# interfaceUART_I2C.net
KiCad netlist of a schematic drawn in Altium Designer
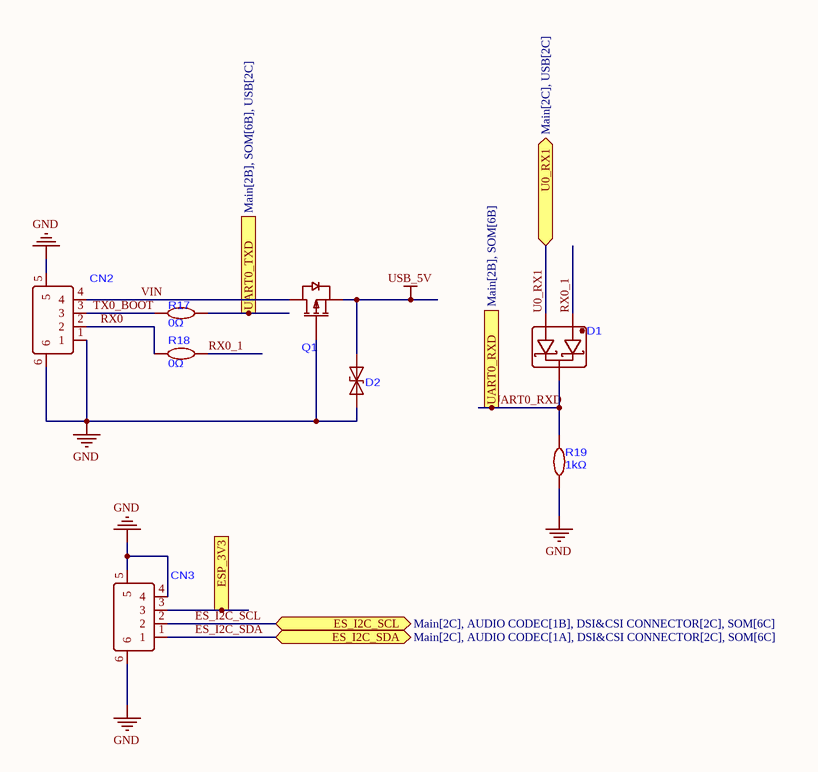
[diagram p0: interfaceUART&I2C.SchDoc]

(export (version "E")
  (design (tool "Eeschema 10.0.6"))
  (components
    (comp (ref "CN2")
      (value "533980471")
      (footprint "CONN-SMD_4P-P1.25_XUNPU_WAFER-GH1.25-4PWB")
      (libsource (lib "Schlib2") (part "533980471"))
    )
    (comp (ref "CN3")
      (value "533980471")
      (footprint "CONN-SMD_4P-P1.25_XUNPU_WAFER-GH1.25-4PWB")
      (libsource (lib "Schlib2") (part "533980471"))
    )
    (comp (ref "D1")
      (value "DIODE ARR SCHOTTKY 30V SOT-23")
      (footprint "SOT-23-3_L2.9-W1.3-P1.90-LS2.4-BR")
      (description "600mA 30V 1 Pair Common Cathode 1V@100mA 200mA SOT-23 Single Diodes RoHS")
      (libsource (lib "Schlib2") (part "BAT54C_C916424"))
    )
    (comp (ref "D2")
      (value "TVS DIODE 5VWM 18.6VC SOD-523")
      (footprint "SOD-523_L1.2-W0.8-LS1.6-BI")
      (description "9.4A@8/20us 18.6V 7.8V 5V SOD-523 TVS Diodes RoHS")
      (libsource (lib "Schlib2") (part "LESD5D5.0CT1G"))
    )
    (comp (ref "Q1")
      (value "MOSFET P-CH 30V 4.3A SOT-23")
      (footprint "2SOT-23-3_L2.9-W1.6-P1.90-LS2.8-BR")
      (description "30V 4.3A 48mΩ@10V 2.5V@250uA 1 P-Channel SOT-23 Single FETs, MOSFETs ROHS")
      (libsource (lib "Schlib2") (part "AO3407A"))
    )
    (comp (ref "R17")
      (value "0Ω")
      (footprint "R0603")
      (description "100mW 0Ω 75V Thick Film Resistor ±5% 0603 Chip Resistor - Surface Mount RoHS")
      (libsource (lib "Schlib2") (part "RC0603JR-070RL"))
    )
    (comp (ref "R18")
      (value "0Ω")
      (footprint "R0603")
      (description "100mW 0Ω 75V Thick Film Resistor ±5% 0603 Chip Resistor - Surface Mount RoHS")
      (libsource (lib "Schlib2") (part "RC0603JR-070RL"))
    )
    (comp (ref "R19")
      (value "1kΩ")
      (footprint "R0603")
      (description "100mW 1kΩ 50V ±100ppm/℃ Thick Film Resistor ±5% 0603 Chip Resistor - Surface Mount ROHS")
      (libsource (lib "Schlib2") (part "RMC 0603 1K J N"))
    )
  )
  (nets
    (net (code "1") (name "/ESP_3V3") (class "Default")
      (node (ref "CN3") (pin "3") (pinfunction "3_3") (pintype "passive"))
    )
    (net (code "2") (name "/ES_I2C_SCL") (class "Default")
      (node (ref "CN3") (pin "2") (pinfunction "2_2") (pintype "passive"))
    )
    (net (code "3") (name "/ES_I2C_SDA") (class "Default")
      (node (ref "CN3") (pin "1") (pinfunction "1_1") (pintype "passive"))
    )
    (net (code "4") (name "/RX0") (class "Default")
      (node (ref "CN2") (pin "2") (pinfunction "2_2") (pintype "passive"))
      (node (ref "R18") (pin "1") (pinfunction "1_1") (pintype "passive"))
    )
    (net (code "5") (name "/RX0_1") (class "Default")
      (node (ref "D1") (pin "1") (pinfunction "1_1") (pintype "passive"))
      (node (ref "R18") (pin "2") (pinfunction "2_2") (pintype "passive"))
    )
    (net (code "6") (name "/TX0_BOOT") (class "Default")
      (node (ref "CN2") (pin "3") (pinfunction "3_3") (pintype "passive"))
      (node (ref "R17") (pin "1") (pinfunction "1_1") (pintype "passive"))
    )
    (net (code "7") (name "/U0_RX1") (class "Default")
      (node (ref "D1") (pin "2") (pinfunction "2_2") (pintype "passive"))
    )
    (net (code "8") (name "/UART0_RXD") (class "Default")
      (node (ref "D1") (pin "3") (pinfunction "3_3") (pintype "passive"))
      (node (ref "R19") (pin "2") (pinfunction "2_2") (pintype "passive"))
    )
    (net (code "9") (name "/UART0_TXD") (class "Default")
      (node (ref "R17") (pin "2") (pinfunction "2_2") (pintype "passive"))
    )
    (net (code "10") (name "/VIN") (class "Default")
      (node (ref "CN2") (pin "4") (pinfunction "4_4") (pintype "passive"))
      (node (ref "Q1") (pin "3") (pinfunction "D_3") (pintype "passive"))
    )
    (net (code "11") (name "GND") (class "Default")
      (node (ref "CN2") (pin "1") (pinfunction "1_1") (pintype "passive"))
      (node (ref "CN2") (pin "5") (pinfunction "5_5") (pintype "passive"))
      (node (ref "CN2") (pin "6") (pinfunction "6_6") (pintype "passive"))
      (node (ref "CN3") (pin "4") (pinfunction "4_4") (pintype "passive"))
      (node (ref "CN3") (pin "5") (pinfunction "5_5") (pintype "passive"))
      (node (ref "CN3") (pin "6") (pinfunction "6_6") (pintype "passive"))
      (node (ref "D2") (pin "1") (pinfunction "K_1") (pintype "passive"))
      (node (ref "Q1") (pin "1") (pinfunction "G_1") (pintype "passive"))
      (node (ref "R19") (pin "1") (pinfunction "1_1") (pintype "passive"))
    )
    (net (code "12") (name "USB_5V") (class "Default")
      (node (ref "D2") (pin "2") (pinfunction "A_2") (pintype "passive"))
      (node (ref "Q1") (pin "2") (pinfunction "S_2") (pintype "passive"))
    )
  )
)
